# Motor.net
KiCad netlist of a schematic drawn in Altium Designer
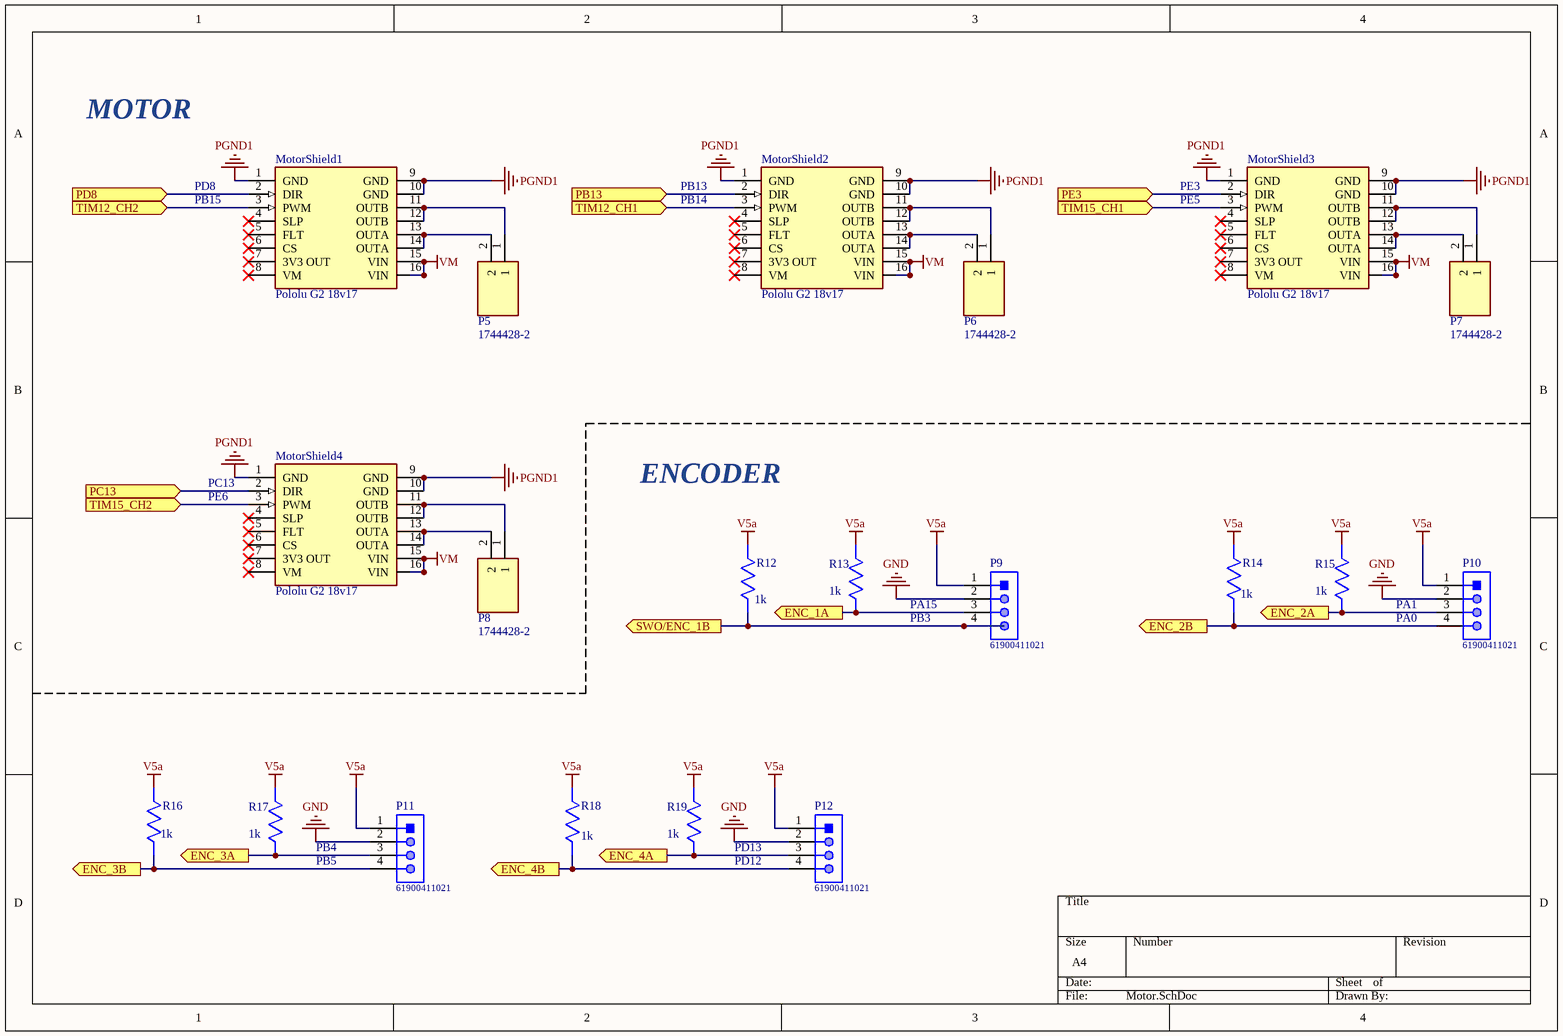
[diagram p0: Motor.SchDoc]

(export (version "E")
  (design (tool "Eeschema 10.0.6"))
  (components
    (comp (ref "MotorShield1")
      (value "Pololu G2 18v17")
      (footprint "SamacSys:Pololu G218V17")
      (description "DC Motor Driver")
      (libsource (lib "SamacSys") (part "Pololu G2 18v17"))
    )
    (comp (ref "MotorShield2")
      (value "Pololu G2 18v17")
      (footprint "SamacSys:Pololu G218V17")
      (description "DC Motor Driver")
      (libsource (lib "SamacSys") (part "Pololu G2 18v17"))
    )
    (comp (ref "MotorShield3")
      (value "Pololu G2 18v17")
      (footprint "SamacSys:Pololu G218V17")
      (description "DC Motor Driver")
      (libsource (lib "SamacSys") (part "Pololu G2 18v17"))
    )
    (comp (ref "MotorShield4")
      (value "Pololu G2 18v17")
      (footprint "SamacSys:Pololu G218V17")
      (description "DC Motor Driver")
      (libsource (lib "SamacSys") (part "Pololu G2 18v17"))
    )
    (comp (ref "P5")
      (value "1744428-2")
      (footprint "SamacSys:17444282")
      (description "Connector")
      (fields (field (name "MOUSER PART NUMBER") "571-1744428-2"))
      (libsource (lib "*") (part "1744428-2"))
    )
    (comp (ref "P6")
      (value "1744428-2")
      (footprint "SamacSys:17444282")
      (description "Connector")
      (fields (field (name "MOUSER PART NUMBER") "571-1744428-2"))
      (libsource (lib "*") (part "1744428-2"))
    )
    (comp (ref "P7")
      (value "1744428-2")
      (footprint "SamacSys:17444282")
      (description "Connector")
      (fields (field (name "MOUSER PART NUMBER") "571-1744428-2"))
      (libsource (lib "*") (part "1744428-2"))
    )
    (comp (ref "P8")
      (value "1744428-2")
      (footprint "SamacSys:17444282")
      (description "Connector")
      (fields (field (name "MOUSER PART NUMBER") "571-1744428-2"))
      (libsource (lib "*") (part "1744428-2"))
    )
    (comp (ref "P9")
      (value "61900411021")
      (footprint "61900411021")
      (description "Male Bottom Locking Header WR-WTB, THT, Right Angled, pitch 2.54 mm, 1 x 4 position")
      (fields (field (name "MANUFACTURER") "Wurth Elektronik") (field (name "PUBLISHER") "WurthElektronik"))
      (libsource (lib "Altium Content Vault") (part "WE-CN-1P-M-R4"))
    )
    (comp (ref "P10")
      (value "61900411021")
      (footprint "61900411021")
      (description "Male Bottom Locking Header WR-WTB, THT, Right Angled, pitch 2.54 mm, 1 x 4 position")
      (fields (field (name "MANUFACTURER") "Wurth Elektronik") (field (name "PUBLISHER") "WurthElektronik"))
      (libsource (lib "Altium Content Vault") (part "WE-CN-1P-M-R4"))
    )
    (comp (ref "P11")
      (value "61900411021")
      (footprint "61900411021")
      (description "Male Bottom Locking Header WR-WTB, THT, Right Angled, pitch 2.54 mm, 1 x 4 position")
      (fields (field (name "MANUFACTURER") "Wurth Elektronik") (field (name "PUBLISHER") "WurthElektronik"))
      (libsource (lib "Altium Content Vault") (part "WE-CN-1P-M-R4"))
    )
    (comp (ref "P12")
      (value "61900411021")
      (footprint "61900411021")
      (description "Male Bottom Locking Header WR-WTB, THT, Right Angled, pitch 2.54 mm, 1 x 4 position")
      (fields (field (name "MANUFACTURER") "Wurth Elektronik") (field (name "PUBLISHER") "WurthElektronik"))
      (libsource (lib "Altium Content Vault") (part "WE-CN-1P-M-R4"))
    )
    (comp (ref "R12")
      (value "1k")
      (footprint "SamacSys:RESC1608X55N")
      (description "Resistor")
      (fields (field (name "MANUFACTURER_PART_NUMBER") "CMP0603-FX-1003ELF"))
      (libsource (lib "SamacSys") (part "CMP0603-FX-1003ELF"))
    )
    (comp (ref "R13")
      (value "1k")
      (footprint "SamacSys:RESC1608X55N")
      (description "Resistor")
      (fields (field (name "MANUFACTURER_PART_NUMBER") "CMP0603-FX-1003ELF"))
      (libsource (lib "SamacSys") (part "CMP0603-FX-1003ELF"))
    )
    (comp (ref "R14")
      (value "1k")
      (footprint "SamacSys:RESC1608X55N")
      (description "Resistor")
      (fields (field (name "MANUFACTURER_PART_NUMBER") "CMP0603-FX-1003ELF"))
      (libsource (lib "SamacSys") (part "CMP0603-FX-1003ELF"))
    )
    (comp (ref "R15")
      (value "1k")
      (footprint "SamacSys:RESC1608X55N")
      (description "Resistor")
      (fields (field (name "MANUFACTURER_PART_NUMBER") "CMP0603-FX-1003ELF"))
      (libsource (lib "SamacSys") (part "CMP0603-FX-1003ELF"))
    )
    (comp (ref "R16")
      (value "1k")
      (footprint "SamacSys:RESC1608X55N")
      (description "Resistor")
      (fields (field (name "MANUFACTURER_PART_NUMBER") "CMP0603-FX-1003ELF"))
      (libsource (lib "SamacSys") (part "CMP0603-FX-1003ELF"))
    )
    (comp (ref "R17")
      (value "1k")
      (footprint "SamacSys:RESC1608X55N")
      (description "Resistor")
      (fields (field (name "MANUFACTURER_PART_NUMBER") "CMP0603-FX-1003ELF"))
      (libsource (lib "SamacSys") (part "CMP0603-FX-1003ELF"))
    )
    (comp (ref "R18")
      (value "1k")
      (footprint "SamacSys:RESC1608X55N")
      (description "Resistor")
      (fields (field (name "MANUFACTURER_PART_NUMBER") "CMP0603-FX-1003ELF"))
      (libsource (lib "SamacSys") (part "CMP0603-FX-1003ELF"))
    )
    (comp (ref "R19")
      (value "1k")
      (footprint "SamacSys:RESC1608X55N")
      (description "Resistor")
      (fields (field (name "MANUFACTURER_PART_NUMBER") "CMP0603-FX-1003ELF"))
      (libsource (lib "SamacSys") (part "CMP0603-FX-1003ELF"))
    )
  )
  (nets
    (net (code "1") (name "/ENC_1A") (class "Default")
      (node (ref "P9") (pin "3") (pinfunction "3_3") (pintype "passive"))
      (node (ref "R13") (pin "1") (pinfunction "1_1") (pintype "passive"))
    )
    (net (code "2") (name "/ENC_2A") (class "Default")
      (node (ref "P10") (pin "3") (pinfunction "3_3") (pintype "passive"))
      (node (ref "R15") (pin "1") (pinfunction "1_1") (pintype "passive"))
    )
    (net (code "3") (name "/ENC_2B") (class "Default")
      (node (ref "P10") (pin "4") (pinfunction "4_4") (pintype "passive"))
      (node (ref "R14") (pin "1") (pinfunction "1_1") (pintype "passive"))
    )
    (net (code "4") (name "/ENC_3A") (class "Default")
      (node (ref "P11") (pin "3") (pinfunction "3_3") (pintype "passive"))
      (node (ref "R17") (pin "1") (pinfunction "1_1") (pintype "passive"))
    )
    (net (code "5") (name "/ENC_3B") (class "Default")
      (node (ref "P11") (pin "4") (pinfunction "4_4") (pintype "passive"))
      (node (ref "R16") (pin "1") (pinfunction "1_1") (pintype "passive"))
    )
    (net (code "6") (name "/ENC_4A") (class "Default")
      (node (ref "P12") (pin "3") (pinfunction "3_3") (pintype "passive"))
      (node (ref "R19") (pin "1") (pinfunction "1_1") (pintype "passive"))
    )
    (net (code "7") (name "/ENC_4B") (class "Default")
      (node (ref "P12") (pin "4") (pinfunction "4_4") (pintype "passive"))
      (node (ref "R18") (pin "1") (pinfunction "1_1") (pintype "passive"))
    )
    (net (code "8") (name "/PB13") (class "Default")
      (node (ref "MotorShield2") (pin "2") (pinfunction "DIR_2") (pintype "input"))
    )
    (net (code "9") (name "/PC13") (class "Default")
      (node (ref "MotorShield4") (pin "2") (pinfunction "DIR_2") (pintype "input"))
    )
    (net (code "10") (name "/PD8") (class "Default")
      (node (ref "MotorShield1") (pin "2") (pinfunction "DIR_2") (pintype "input"))
    )
    (net (code "11") (name "/PE3") (class "Default")
      (node (ref "MotorShield3") (pin "2") (pinfunction "DIR_2") (pintype "input"))
    )
    (net (code "12") (name "/SWO{slash}ENC_1B") (class "Default")
      (node (ref "P9") (pin "4") (pinfunction "4_4") (pintype "passive"))
      (node (ref "R12") (pin "1") (pinfunction "1_1") (pintype "passive"))
    )
    (net (code "13") (name "/TIM12_CH1") (class "Default")
      (node (ref "MotorShield2") (pin "3") (pinfunction "PWM_3") (pintype "input"))
    )
    (net (code "14") (name "/TIM12_CH2") (class "Default")
      (node (ref "MotorShield1") (pin "3") (pinfunction "PWM_3") (pintype "input"))
    )
    (net (code "15") (name "/TIM15_CH1") (class "Default")
      (node (ref "MotorShield3") (pin "3") (pinfunction "PWM_3") (pintype "input"))
    )
    (net (code "16") (name "/TIM15_CH2") (class "Default")
      (node (ref "MotorShield4") (pin "3") (pinfunction "PWM_3") (pintype "input"))
    )
    (net (code "17") (name "GND") (class "Default")
      (node (ref "P10") (pin "2") (pinfunction "2_2") (pintype "passive"))
      (node (ref "P11") (pin "2") (pinfunction "2_2") (pintype "passive"))
      (node (ref "P12") (pin "2") (pinfunction "2_2") (pintype "passive"))
      (node (ref "P9") (pin "2") (pinfunction "2_2") (pintype "passive"))
    )
    (net (code "18") (name "Net-(MotorShield1-OUTA-Pad13)") (class "Default")
      (node (ref "MotorShield1") (pin "13") (pinfunction "OUTA_13") (pintype "tri_state"))
      (node (ref "MotorShield1") (pin "14") (pinfunction "OUTA_14") (pintype "tri_state"))
      (node (ref "P5") (pin "2") (pinfunction "2_2") (pintype "passive"))
    )
    (net (code "19") (name "Net-(MotorShield1-OUTB-Pad11)") (class "Default")
      (node (ref "MotorShield1") (pin "11") (pinfunction "OUTB_11") (pintype "tri_state"))
      (node (ref "MotorShield1") (pin "12") (pinfunction "OUTB_12") (pintype "tri_state"))
      (node (ref "P5") (pin "1") (pinfunction "1_1") (pintype "passive"))
    )
    (net (code "20") (name "Net-(MotorShield2-OUTA-Pad13)") (class "Default")
      (node (ref "MotorShield2") (pin "13") (pinfunction "OUTA_13") (pintype "tri_state"))
      (node (ref "MotorShield2") (pin "14") (pinfunction "OUTA_14") (pintype "tri_state"))
      (node (ref "P6") (pin "2") (pinfunction "2_2") (pintype "passive"))
    )
    (net (code "21") (name "Net-(MotorShield2-OUTB-Pad11)") (class "Default")
      (node (ref "MotorShield2") (pin "11") (pinfunction "OUTB_11") (pintype "tri_state"))
      (node (ref "MotorShield2") (pin "12") (pinfunction "OUTB_12") (pintype "tri_state"))
      (node (ref "P6") (pin "1") (pinfunction "1_1") (pintype "passive"))
    )
    (net (code "22") (name "Net-(MotorShield3-OUTA-Pad13)") (class "Default")
      (node (ref "MotorShield3") (pin "13") (pinfunction "OUTA_13") (pintype "tri_state"))
      (node (ref "MotorShield3") (pin "14") (pinfunction "OUTA_14") (pintype "tri_state"))
      (node (ref "P7") (pin "2") (pinfunction "2_2") (pintype "passive"))
    )
    (net (code "23") (name "Net-(MotorShield3-OUTB-Pad11)") (class "Default")
      (node (ref "MotorShield3") (pin "11") (pinfunction "OUTB_11") (pintype "tri_state"))
      (node (ref "MotorShield3") (pin "12") (pinfunction "OUTB_12") (pintype "tri_state"))
      (node (ref "P7") (pin "1") (pinfunction "1_1") (pintype "passive"))
    )
    (net (code "24") (name "Net-(MotorShield4-OUTA-Pad13)") (class "Default")
      (node (ref "MotorShield4") (pin "13") (pinfunction "OUTA_13") (pintype "tri_state"))
      (node (ref "MotorShield4") (pin "14") (pinfunction "OUTA_14") (pintype "tri_state"))
      (node (ref "P8") (pin "2") (pinfunction "2_2") (pintype "passive"))
    )
    (net (code "25") (name "Net-(MotorShield4-OUTB-Pad11)") (class "Default")
      (node (ref "MotorShield4") (pin "11") (pinfunction "OUTB_11") (pintype "tri_state"))
      (node (ref "MotorShield4") (pin "12") (pinfunction "OUTB_12") (pintype "tri_state"))
      (node (ref "P8") (pin "1") (pinfunction "1_1") (pintype "passive"))
    )
    (net (code "26") (name "PGND1") (class "Default")
      (node (ref "MotorShield1") (pin "1") (pinfunction "GND_1") (pintype "tri_state"))
      (node (ref "MotorShield1") (pin "10") (pinfunction "GND_10") (pintype "tri_state"))
      (node (ref "MotorShield1") (pin "9") (pinfunction "GND_9") (pintype "passive"))
      (node (ref "MotorShield2") (pin "1") (pinfunction "GND_1") (pintype "tri_state"))
      (node (ref "MotorShield2") (pin "10") (pinfunction "GND_10") (pintype "tri_state"))
      (node (ref "MotorShield2") (pin "9") (pinfunction "GND_9") (pintype "passive"))
      (node (ref "MotorShield3") (pin "1") (pinfunction "GND_1") (pintype "tri_state"))
      (node (ref "MotorShield3") (pin "10") (pinfunction "GND_10") (pintype "tri_state"))
      (node (ref "MotorShield3") (pin "9") (pinfunction "GND_9") (pintype "passive"))
      (node (ref "MotorShield4") (pin "1") (pinfunction "GND_1") (pintype "tri_state"))
      (node (ref "MotorShield4") (pin "10") (pinfunction "GND_10") (pintype "tri_state"))
      (node (ref "MotorShield4") (pin "9") (pinfunction "GND_9") (pintype "passive"))
    )
    (net (code "27") (name "V5a") (class "Default")
      (node (ref "P10") (pin "1") (pinfunction "1_1") (pintype "passive"))
      (node (ref "P11") (pin "1") (pinfunction "1_1") (pintype "passive"))
      (node (ref "P12") (pin "1") (pinfunction "1_1") (pintype "passive"))
      (node (ref "P9") (pin "1") (pinfunction "1_1") (pintype "passive"))
      (node (ref "R12") (pin "2") (pinfunction "2_2") (pintype "passive"))
      (node (ref "R13") (pin "2") (pinfunction "2_2") (pintype "passive"))
      (node (ref "R14") (pin "2") (pinfunction "2_2") (pintype "passive"))
      (node (ref "R15") (pin "2") (pinfunction "2_2") (pintype "passive"))
      (node (ref "R16") (pin "2") (pinfunction "2_2") (pintype "passive"))
      (node (ref "R17") (pin "2") (pinfunction "2_2") (pintype "passive"))
      (node (ref "R18") (pin "2") (pinfunction "2_2") (pintype "passive"))
      (node (ref "R19") (pin "2") (pinfunction "2_2") (pintype "passive"))
    )
    (net (code "28") (name "VM") (class "Default")
      (node (ref "MotorShield1") (pin "15") (pinfunction "VIN_15") (pintype "power_in"))
      (node (ref "MotorShield1") (pin "16") (pinfunction "VIN_16") (pintype "power_in"))
      (node (ref "MotorShield2") (pin "15") (pinfunction "VIN_15") (pintype "power_in"))
      (node (ref "MotorShield2") (pin "16") (pinfunction "VIN_16") (pintype "power_in"))
      (node (ref "MotorShield3") (pin "15") (pinfunction "VIN_15") (pintype "power_in"))
      (node (ref "MotorShield3") (pin "16") (pinfunction "VIN_16") (pintype "power_in"))
      (node (ref "MotorShield4") (pin "15") (pinfunction "VIN_15") (pintype "power_in"))
      (node (ref "MotorShield4") (pin "16") (pinfunction "VIN_16") (pintype "power_in"))
    )
    (net (code "29") (name "unconnected-(MotorShield1-3V3_OUT-Pad7)") (class "Default")
      (node (ref "MotorShield1") (pin "7") (pinfunction "3V3_OUT_7") (pintype "passive+no_connect"))
    )
    (net (code "30") (name "unconnected-(MotorShield1-CS-Pad6)") (class "Default")
      (node (ref "MotorShield1") (pin "6") (pinfunction "CS_6") (pintype "passive+no_connect"))
    )
    (net (code "31") (name "unconnected-(MotorShield1-FLT-Pad5)") (class "Default")
      (node (ref "MotorShield1") (pin "5") (pinfunction "FLT_5") (pintype "passive+no_connect"))
    )
    (net (code "32") (name "unconnected-(MotorShield1-SLP-Pad4)") (class "Default")
      (node (ref "MotorShield1") (pin "4") (pinfunction "SLP_4") (pintype "passive+no_connect"))
    )
    (net (code "33") (name "unconnected-(MotorShield1-VM-Pad8)") (class "Default")
      (node (ref "MotorShield1") (pin "8") (pinfunction "VM_8") (pintype "power_in+no_connect"))
    )
    (net (code "34") (name "unconnected-(MotorShield2-3V3_OUT-Pad7)") (class "Default")
      (node (ref "MotorShield2") (pin "7") (pinfunction "3V3_OUT_7") (pintype "passive+no_connect"))
    )
    (net (code "35") (name "unconnected-(MotorShield2-CS-Pad6)") (class "Default")
      (node (ref "MotorShield2") (pin "6") (pinfunction "CS_6") (pintype "passive+no_connect"))
    )
    (net (code "36") (name "unconnected-(MotorShield2-FLT-Pad5)") (class "Default")
      (node (ref "MotorShield2") (pin "5") (pinfunction "FLT_5") (pintype "passive+no_connect"))
    )
    (net (code "37") (name "unconnected-(MotorShield2-SLP-Pad4)") (class "Default")
      (node (ref "MotorShield2") (pin "4") (pinfunction "SLP_4") (pintype "passive+no_connect"))
    )
    (net (code "38") (name "unconnected-(MotorShield2-VM-Pad8)") (class "Default")
      (node (ref "MotorShield2") (pin "8") (pinfunction "VM_8") (pintype "power_in+no_connect"))
    )
    (net (code "39") (name "unconnected-(MotorShield3-3V3_OUT-Pad7)") (class "Default")
      (node (ref "MotorShield3") (pin "7") (pinfunction "3V3_OUT_7") (pintype "passive+no_connect"))
    )
    (net (code "40") (name "unconnected-(MotorShield3-CS-Pad6)") (class "Default")
      (node (ref "MotorShield3") (pin "6") (pinfunction "CS_6") (pintype "passive+no_connect"))
    )
    (net (code "41") (name "unconnected-(MotorShield3-FLT-Pad5)") (class "Default")
      (node (ref "MotorShield3") (pin "5") (pinfunction "FLT_5") (pintype "passive+no_connect"))
    )
    (net (code "42") (name "unconnected-(MotorShield3-SLP-Pad4)") (class "Default")
      (node (ref "MotorShield3") (pin "4") (pinfunction "SLP_4") (pintype "passive+no_connect"))
    )
    (net (code "43") (name "unconnected-(MotorShield3-VM-Pad8)") (class "Default")
      (node (ref "MotorShield3") (pin "8") (pinfunction "VM_8") (pintype "power_in+no_connect"))
    )
    (net (code "44") (name "unconnected-(MotorShield4-3V3_OUT-Pad7)") (class "Default")
      (node (ref "MotorShield4") (pin "7") (pinfunction "3V3_OUT_7") (pintype "passive+no_connect"))
    )
    (net (code "45") (name "unconnected-(MotorShield4-CS-Pad6)") (class "Default")
      (node (ref "MotorShield4") (pin "6") (pinfunction "CS_6") (pintype "passive+no_connect"))
    )
    (net (code "46") (name "unconnected-(MotorShield4-FLT-Pad5)") (class "Default")
      (node (ref "MotorShield4") (pin "5") (pinfunction "FLT_5") (pintype "passive+no_connect"))
    )
    (net (code "47") (name "unconnected-(MotorShield4-SLP-Pad4)") (class "Default")
      (node (ref "MotorShield4") (pin "4") (pinfunction "SLP_4") (pintype "passive+no_connect"))
    )
    (net (code "48") (name "unconnected-(MotorShield4-VM-Pad8)") (class "Default")
      (node (ref "MotorShield4") (pin "8") (pinfunction "VM_8") (pintype "power_in+no_connect"))
    )
  )
)
